# CRSC0003.net
KiCad netlist of a schematic drawn in Altium Designer
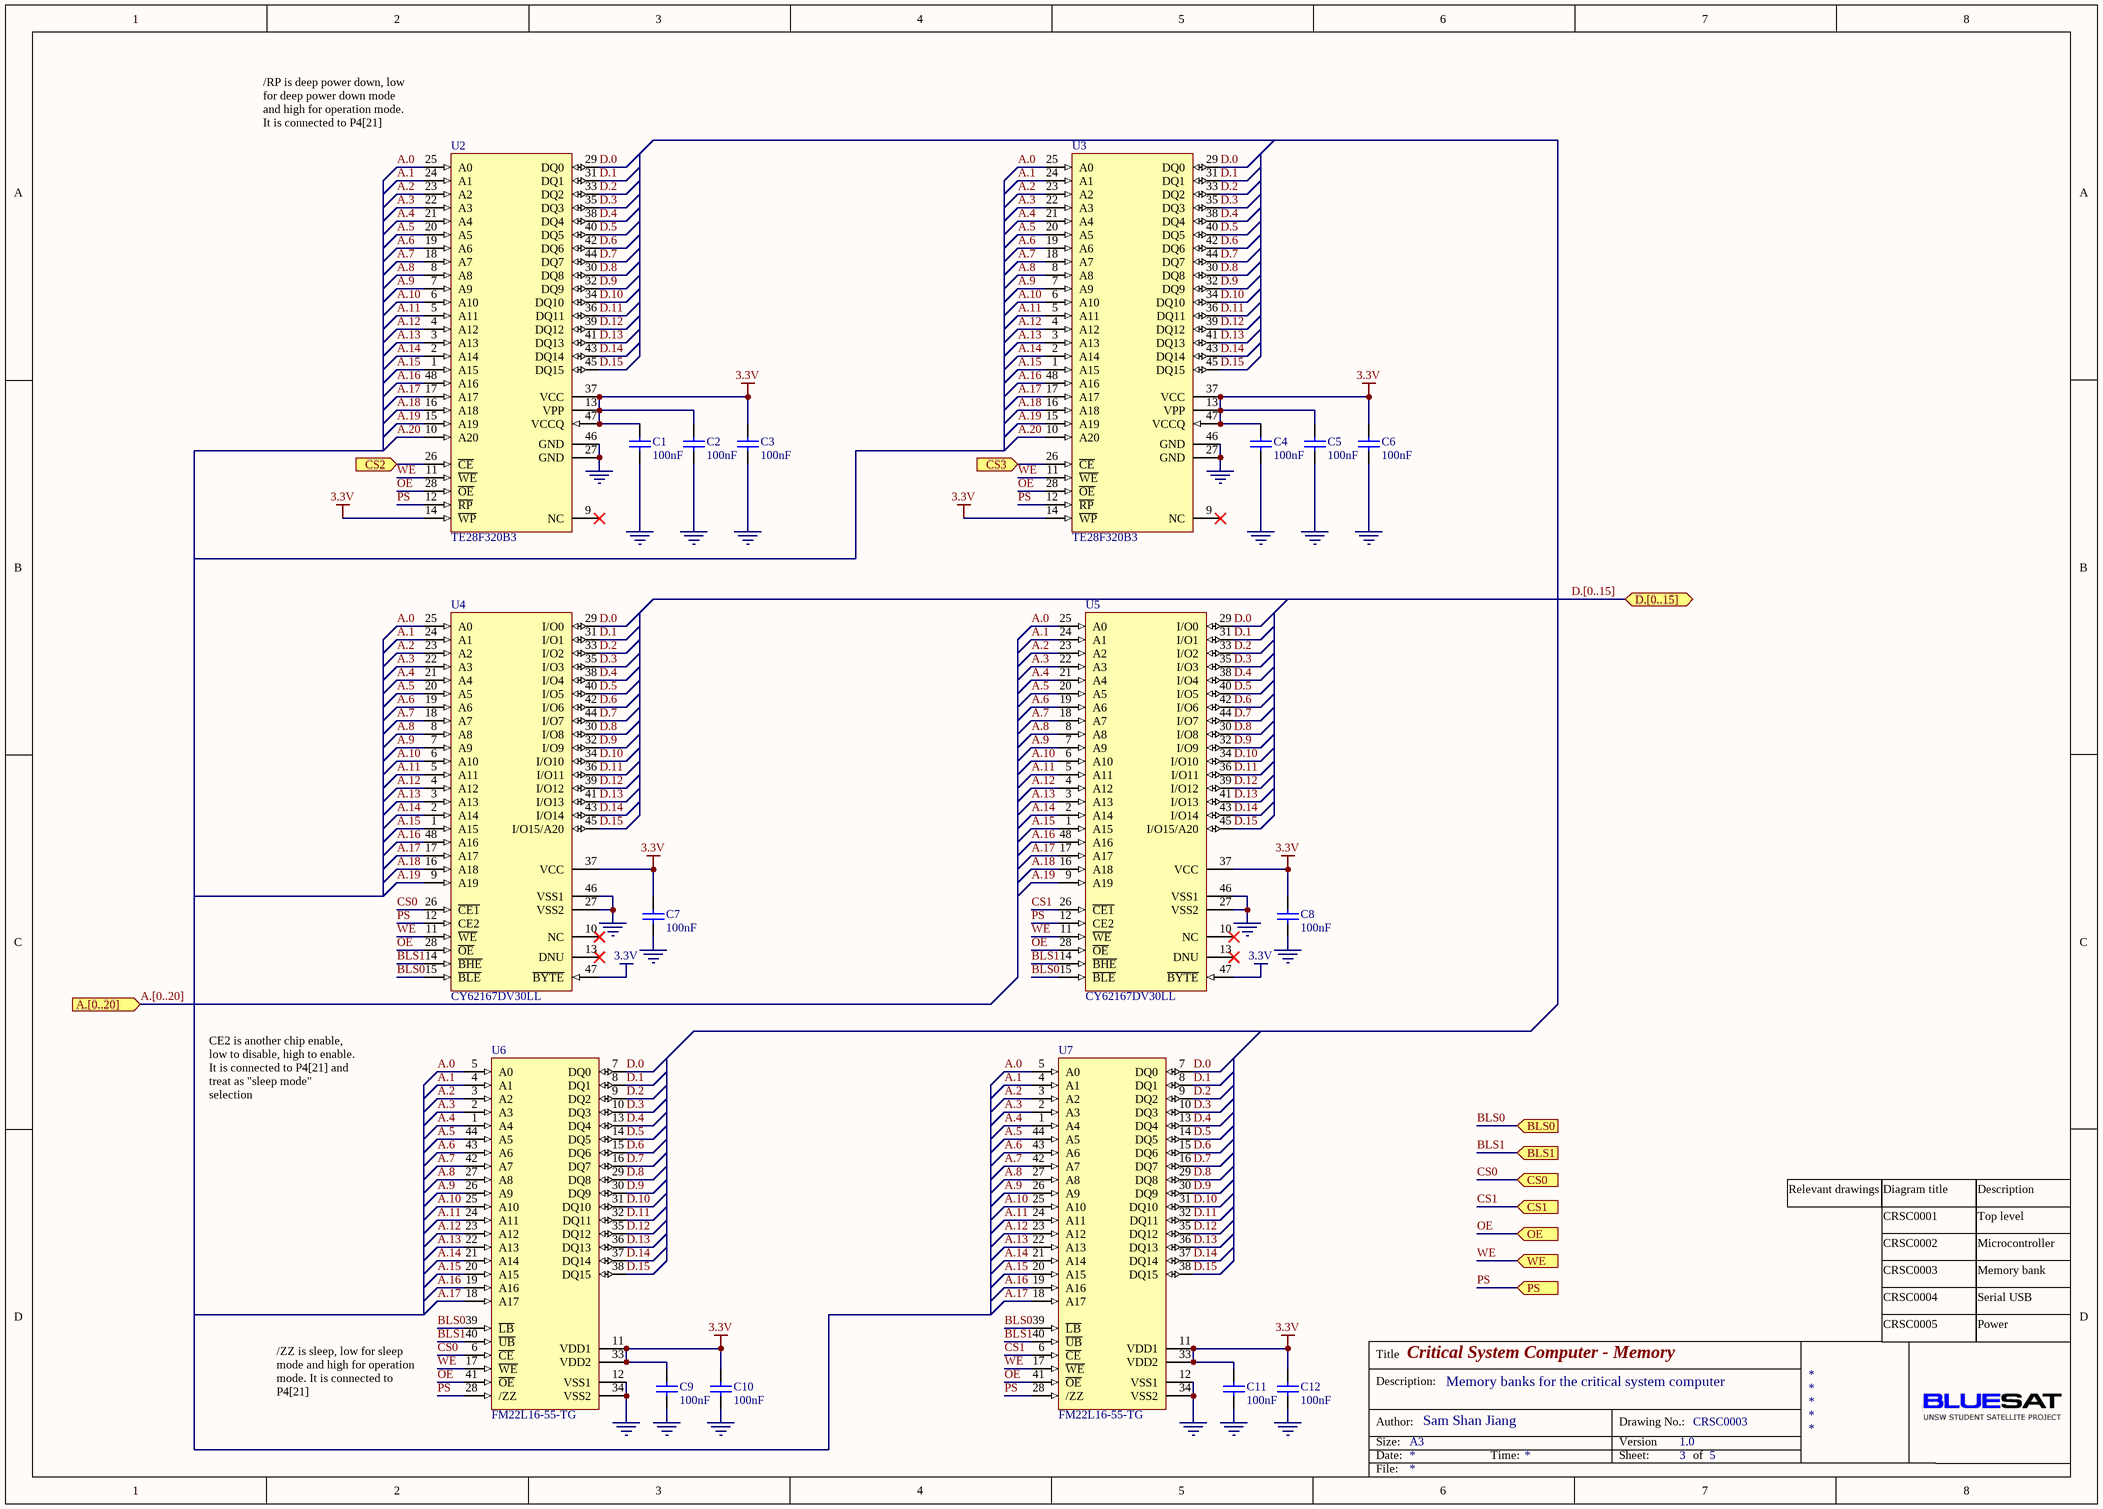
[diagram p0: CRSC0003.SchDoc]

(export (version "E")
  (design (tool "Eeschema 10.0.6"))
  (components
    (comp (ref "C1")
      (value "100nF")
      (footprint "0805")
      (description "Capacitor")
      (fields
        (field (name "MANUFACTURER") "Generic Components")
        (field (name "PUBLISHER") "Altium Hobart Technology Centre")
      )
      (libsource (lib "SELF-MADE_1004") (part "Cap"))
    )
    (comp (ref "C2")
      (value "100nF")
      (footprint "0805")
      (description "Capacitor")
      (fields
        (field (name "MANUFACTURER") "Generic Components")
        (field (name "PUBLISHER") "Altium Hobart Technology Centre")
      )
      (libsource (lib "SELF-MADE_1004") (part "Cap"))
    )
    (comp (ref "C3")
      (value "100nF")
      (footprint "0805")
      (description "Capacitor")
      (fields
        (field (name "MANUFACTURER") "Generic Components")
        (field (name "PUBLISHER") "Altium Hobart Technology Centre")
      )
      (libsource (lib "SELF-MADE_1004") (part "Cap"))
    )
    (comp (ref "C4")
      (value "100nF")
      (footprint "0805")
      (description "Capacitor")
      (fields
        (field (name "MANUFACTURER") "Generic Components")
        (field (name "PUBLISHER") "Altium Hobart Technology Centre")
      )
      (libsource (lib "SELF-MADE_1004") (part "Cap"))
    )
    (comp (ref "C5")
      (value "100nF")
      (footprint "0805")
      (description "Capacitor")
      (fields
        (field (name "MANUFACTURER") "Generic Components")
        (field (name "PUBLISHER") "Altium Hobart Technology Centre")
      )
      (libsource (lib "SELF-MADE_1004") (part "Cap"))
    )
    (comp (ref "C6")
      (value "100nF")
      (footprint "0805")
      (description "Capacitor")
      (fields
        (field (name "MANUFACTURER") "Generic Components")
        (field (name "PUBLISHER") "Altium Hobart Technology Centre")
      )
      (libsource (lib "SELF-MADE_1004") (part "Cap"))
    )
    (comp (ref "C7")
      (value "100nF")
      (footprint "0805")
      (description "Capacitor")
      (fields
        (field (name "MANUFACTURER") "Generic Components")
        (field (name "PUBLISHER") "Altium Hobart Technology Centre")
      )
      (libsource (lib "SELF-MADE_1004") (part "Cap"))
    )
    (comp (ref "C8")
      (value "100nF")
      (footprint "0805")
      (description "Capacitor")
      (fields
        (field (name "MANUFACTURER") "Generic Components")
        (field (name "PUBLISHER") "Altium Hobart Technology Centre")
      )
      (libsource (lib "SELF-MADE_1004") (part "Cap"))
    )
    (comp (ref "C9")
      (value "100nF")
      (footprint "0805")
      (description "Capacitor")
      (fields
        (field (name "MANUFACTURER") "Generic Components")
        (field (name "PUBLISHER") "Altium Hobart Technology Centre")
      )
      (libsource (lib "SELF-MADE_1004") (part "Cap"))
    )
    (comp (ref "C10")
      (value "100nF")
      (footprint "0805")
      (description "Capacitor")
      (fields
        (field (name "MANUFACTURER") "Generic Components")
        (field (name "PUBLISHER") "Altium Hobart Technology Centre")
      )
      (libsource (lib "SELF-MADE_1004") (part "Cap"))
    )
    (comp (ref "C11")
      (value "100nF")
      (footprint "0805")
      (description "Capacitor")
      (fields
        (field (name "MANUFACTURER") "Generic Components")
        (field (name "PUBLISHER") "Altium Hobart Technology Centre")
      )
      (libsource (lib "SELF-MADE_1004") (part "Cap"))
    )
    (comp (ref "C12")
      (value "100nF")
      (footprint "0805")
      (description "Capacitor")
      (fields
        (field (name "MANUFACTURER") "Generic Components")
        (field (name "PUBLISHER") "Altium Hobart Technology Centre")
      )
      (libsource (lib "SELF-MADE_1004") (part "Cap"))
    )
    (comp (ref "U2")
      (value "TE28F320B3")
      (footprint "TSOP48_L")
      (description "32-Mbit (2M x 16) Advanced Boot Block Flash Memory")
      (fields (field (name "PUBLISHER") "Altium Limited"))
      (libsource (lib "SELF-MADE_1505") (part "TE28F320B3"))
    )
    (comp (ref "U3")
      (value "TE28F320B3")
      (footprint "TSOP48_L")
      (description "32-Mbit (2M x 16) Advanced Boot Block Flash Memory")
      (fields (field (name "PUBLISHER") "Altium Limited"))
      (libsource (lib "SELF-MADE_1505") (part "TE28F320B3"))
    )
    (comp (ref "U4")
      (value "CY62167DV30LL")
      (footprint "TSOP48_L")
      (description "16-Mbit (1M x 16) Static RAM")
      (fields (field (name "PUBLISHER") "Altium Limited"))
      (libsource (lib "SELF-MADE_1505") (part "CY62167DV30LL"))
    )
    (comp (ref "U5")
      (value "CY62167DV30LL")
      (footprint "TSOP48_L")
      (description "16-Mbit (1M x 16) Static RAM")
      (fields (field (name "PUBLISHER") "Altium Limited"))
      (libsource (lib "SELF-MADE_1505") (part "CY62167DV30LL"))
    )
    (comp (ref "U6")
      (value "FM22L16-55-TG")
      (footprint "TSOP2-44_M")
      (description "FRAM, 2MB, 3V, 60NS, 44TSOP2")
      (libsource (lib "SELF-MADE_1004") (part "FM22L16-55-TG"))
    )
    (comp (ref "U7")
      (value "FM22L16-55-TG")
      (footprint "TSOP2-44_M")
      (description "FRAM, 2MB, 3V, 60NS, 44TSOP2")
      (libsource (lib "SELF-MADE_1004") (part "FM22L16-55-TG"))
    )
  )
  (nets
    (net (code "1") (name "/A.0") (class "Default")
      (node (ref "U2") (pin "25") (pinfunction "A0_25") (pintype "input"))
      (node (ref "U3") (pin "25") (pinfunction "A0_25") (pintype "input"))
      (node (ref "U4") (pin "25") (pinfunction "A0_25") (pintype "input"))
      (node (ref "U5") (pin "25") (pinfunction "A0_25") (pintype "input"))
      (node (ref "U6") (pin "5") (pinfunction "A0_5") (pintype "input"))
      (node (ref "U7") (pin "5") (pinfunction "A0_5") (pintype "input"))
    )
    (net (code "2") (name "/A.1") (class "Default")
      (node (ref "U2") (pin "24") (pinfunction "A1_24") (pintype "input"))
      (node (ref "U3") (pin "24") (pinfunction "A1_24") (pintype "input"))
      (node (ref "U4") (pin "24") (pinfunction "A1_24") (pintype "input"))
      (node (ref "U5") (pin "24") (pinfunction "A1_24") (pintype "input"))
      (node (ref "U6") (pin "4") (pinfunction "A1_4") (pintype "input"))
      (node (ref "U7") (pin "4") (pinfunction "A1_4") (pintype "input"))
    )
    (net (code "3") (name "/A.2") (class "Default")
      (node (ref "U2") (pin "23") (pinfunction "A2_23") (pintype "input"))
      (node (ref "U3") (pin "23") (pinfunction "A2_23") (pintype "input"))
      (node (ref "U4") (pin "23") (pinfunction "A2_23") (pintype "input"))
      (node (ref "U5") (pin "23") (pinfunction "A2_23") (pintype "input"))
      (node (ref "U6") (pin "3") (pinfunction "A2_3") (pintype "input"))
      (node (ref "U7") (pin "3") (pinfunction "A2_3") (pintype "input"))
    )
    (net (code "4") (name "/A.3") (class "Default")
      (node (ref "U2") (pin "22") (pinfunction "A3_22") (pintype "input"))
      (node (ref "U3") (pin "22") (pinfunction "A3_22") (pintype "input"))
      (node (ref "U4") (pin "22") (pinfunction "A3_22") (pintype "input"))
      (node (ref "U5") (pin "22") (pinfunction "A3_22") (pintype "input"))
      (node (ref "U6") (pin "2") (pinfunction "A3_2") (pintype "input"))
      (node (ref "U7") (pin "2") (pinfunction "A3_2") (pintype "input"))
    )
    (net (code "5") (name "/A.4") (class "Default")
      (node (ref "U2") (pin "21") (pinfunction "A4_21") (pintype "input"))
      (node (ref "U3") (pin "21") (pinfunction "A4_21") (pintype "input"))
      (node (ref "U4") (pin "21") (pinfunction "A4_21") (pintype "input"))
      (node (ref "U5") (pin "21") (pinfunction "A4_21") (pintype "input"))
      (node (ref "U6") (pin "1") (pinfunction "A4_1") (pintype "input"))
      (node (ref "U7") (pin "1") (pinfunction "A4_1") (pintype "input"))
    )
    (net (code "6") (name "/A.5") (class "Default")
      (node (ref "U2") (pin "20") (pinfunction "A5_20") (pintype "input"))
      (node (ref "U3") (pin "20") (pinfunction "A5_20") (pintype "input"))
      (node (ref "U4") (pin "20") (pinfunction "A5_20") (pintype "input"))
      (node (ref "U5") (pin "20") (pinfunction "A5_20") (pintype "input"))
      (node (ref "U6") (pin "44") (pinfunction "A5_44") (pintype "input"))
      (node (ref "U7") (pin "44") (pinfunction "A5_44") (pintype "input"))
    )
    (net (code "7") (name "/A.6") (class "Default")
      (node (ref "U2") (pin "19") (pinfunction "A6_19") (pintype "input"))
      (node (ref "U3") (pin "19") (pinfunction "A6_19") (pintype "input"))
      (node (ref "U4") (pin "19") (pinfunction "A6_19") (pintype "input"))
      (node (ref "U5") (pin "19") (pinfunction "A6_19") (pintype "input"))
      (node (ref "U6") (pin "43") (pinfunction "A6_43") (pintype "input"))
      (node (ref "U7") (pin "43") (pinfunction "A6_43") (pintype "input"))
    )
    (net (code "8") (name "/A.7") (class "Default")
      (node (ref "U2") (pin "18") (pinfunction "A7_18") (pintype "input"))
      (node (ref "U3") (pin "18") (pinfunction "A7_18") (pintype "input"))
      (node (ref "U4") (pin "18") (pinfunction "A7_18") (pintype "input"))
      (node (ref "U5") (pin "18") (pinfunction "A7_18") (pintype "input"))
      (node (ref "U6") (pin "42") (pinfunction "A7_42") (pintype "input"))
      (node (ref "U7") (pin "42") (pinfunction "A7_42") (pintype "input"))
    )
    (net (code "9") (name "/A.8") (class "Default")
      (node (ref "U2") (pin "8") (pinfunction "A8_8") (pintype "input"))
      (node (ref "U3") (pin "8") (pinfunction "A8_8") (pintype "input"))
      (node (ref "U4") (pin "8") (pinfunction "A8_8") (pintype "input"))
      (node (ref "U5") (pin "8") (pinfunction "A8_8") (pintype "input"))
      (node (ref "U6") (pin "27") (pinfunction "A8_27") (pintype "input"))
      (node (ref "U7") (pin "27") (pinfunction "A8_27") (pintype "input"))
    )
    (net (code "10") (name "/A.9") (class "Default")
      (node (ref "U2") (pin "7") (pinfunction "A9_7") (pintype "input"))
      (node (ref "U3") (pin "7") (pinfunction "A9_7") (pintype "input"))
      (node (ref "U4") (pin "7") (pinfunction "A9_7") (pintype "input"))
      (node (ref "U5") (pin "7") (pinfunction "A9_7") (pintype "input"))
      (node (ref "U6") (pin "26") (pinfunction "A9_26") (pintype "input"))
      (node (ref "U7") (pin "26") (pinfunction "A9_26") (pintype "input"))
    )
    (net (code "11") (name "/A.10") (class "Default")
      (node (ref "U2") (pin "6") (pinfunction "A10_6") (pintype "input"))
      (node (ref "U3") (pin "6") (pinfunction "A10_6") (pintype "input"))
      (node (ref "U4") (pin "6") (pinfunction "A10_6") (pintype "input"))
      (node (ref "U5") (pin "6") (pinfunction "A10_6") (pintype "input"))
      (node (ref "U6") (pin "25") (pinfunction "A10_25") (pintype "input"))
      (node (ref "U7") (pin "25") (pinfunction "A10_25") (pintype "input"))
    )
    (net (code "12") (name "/A.11") (class "Default")
      (node (ref "U2") (pin "5") (pinfunction "A11_5") (pintype "input"))
      (node (ref "U3") (pin "5") (pinfunction "A11_5") (pintype "input"))
      (node (ref "U4") (pin "5") (pinfunction "A11_5") (pintype "input"))
      (node (ref "U5") (pin "5") (pinfunction "A11_5") (pintype "input"))
      (node (ref "U6") (pin "24") (pinfunction "A11_24") (pintype "input"))
      (node (ref "U7") (pin "24") (pinfunction "A11_24") (pintype "input"))
    )
    (net (code "13") (name "/A.12") (class "Default")
      (node (ref "U2") (pin "4") (pinfunction "A12_4") (pintype "input"))
      (node (ref "U3") (pin "4") (pinfunction "A12_4") (pintype "input"))
      (node (ref "U4") (pin "4") (pinfunction "A12_4") (pintype "input"))
      (node (ref "U5") (pin "4") (pinfunction "A12_4") (pintype "input"))
      (node (ref "U6") (pin "23") (pinfunction "A12_23") (pintype "input"))
      (node (ref "U7") (pin "23") (pinfunction "A12_23") (pintype "input"))
    )
    (net (code "14") (name "/A.13") (class "Default")
      (node (ref "U2") (pin "3") (pinfunction "A13_3") (pintype "input"))
      (node (ref "U3") (pin "3") (pinfunction "A13_3") (pintype "input"))
      (node (ref "U4") (pin "3") (pinfunction "A13_3") (pintype "input"))
      (node (ref "U5") (pin "3") (pinfunction "A13_3") (pintype "input"))
      (node (ref "U6") (pin "22") (pinfunction "A13_22") (pintype "input"))
      (node (ref "U7") (pin "22") (pinfunction "A13_22") (pintype "input"))
    )
    (net (code "15") (name "/A.14") (class "Default")
      (node (ref "U2") (pin "2") (pinfunction "A14_2") (pintype "input"))
      (node (ref "U3") (pin "2") (pinfunction "A14_2") (pintype "input"))
      (node (ref "U4") (pin "2") (pinfunction "A14_2") (pintype "input"))
      (node (ref "U5") (pin "2") (pinfunction "A14_2") (pintype "input"))
      (node (ref "U6") (pin "21") (pinfunction "A14_21") (pintype "input"))
      (node (ref "U7") (pin "21") (pinfunction "A14_21") (pintype "input"))
    )
    (net (code "16") (name "/A.15") (class "Default")
      (node (ref "U2") (pin "1") (pinfunction "A15_1") (pintype "input"))
      (node (ref "U3") (pin "1") (pinfunction "A15_1") (pintype "input"))
      (node (ref "U4") (pin "1") (pinfunction "A15_1") (pintype "input"))
      (node (ref "U5") (pin "1") (pinfunction "A15_1") (pintype "input"))
      (node (ref "U6") (pin "20") (pinfunction "A15_20") (pintype "input"))
      (node (ref "U7") (pin "20") (pinfunction "A15_20") (pintype "input"))
    )
    (net (code "17") (name "/A.16") (class "Default")
      (node (ref "U2") (pin "48") (pinfunction "A16_48") (pintype "input"))
      (node (ref "U3") (pin "48") (pinfunction "A16_48") (pintype "input"))
      (node (ref "U4") (pin "48") (pinfunction "A16_48") (pintype "input"))
      (node (ref "U5") (pin "48") (pinfunction "A16_48") (pintype "input"))
      (node (ref "U6") (pin "19") (pinfunction "A16_19") (pintype "input"))
      (node (ref "U7") (pin "19") (pinfunction "A16_19") (pintype "input"))
    )
    (net (code "18") (name "/A.17") (class "Default")
      (node (ref "U2") (pin "17") (pinfunction "A17_17") (pintype "input"))
      (node (ref "U3") (pin "17") (pinfunction "A17_17") (pintype "input"))
      (node (ref "U4") (pin "17") (pinfunction "A17_17") (pintype "input"))
      (node (ref "U5") (pin "17") (pinfunction "A17_17") (pintype "input"))
      (node (ref "U6") (pin "18") (pinfunction "A17_18") (pintype "input"))
      (node (ref "U7") (pin "18") (pinfunction "A17_18") (pintype "input"))
    )
    (net (code "19") (name "/A.18") (class "Default")
      (node (ref "U2") (pin "16") (pinfunction "A18_16") (pintype "input"))
      (node (ref "U3") (pin "16") (pinfunction "A18_16") (pintype "input"))
      (node (ref "U4") (pin "16") (pinfunction "A18_16") (pintype "input"))
      (node (ref "U5") (pin "16") (pinfunction "A18_16") (pintype "input"))
    )
    (net (code "20") (name "/A.19") (class "Default")
      (node (ref "U2") (pin "15") (pinfunction "A19_15") (pintype "input"))
      (node (ref "U3") (pin "15") (pinfunction "A19_15") (pintype "input"))
      (node (ref "U4") (pin "9") (pinfunction "A19_9") (pintype "input"))
      (node (ref "U5") (pin "9") (pinfunction "A19_9") (pintype "input"))
    )
    (net (code "21") (name "/A.20") (class "Default")
      (node (ref "U2") (pin "10") (pinfunction "A20_10") (pintype "input"))
      (node (ref "U3") (pin "10") (pinfunction "A20_10") (pintype "input"))
    )
    (net (code "23") (name "/BLS0") (class "Default")
      (node (ref "U4") (pin "15") (pinfunction "~{BLE}_15") (pintype "input"))
      (node (ref "U5") (pin "15") (pinfunction "~{BLE}_15") (pintype "input"))
      (node (ref "U6") (pin "39") (pinfunction "~{LB}_39") (pintype "input"))
      (node (ref "U7") (pin "39") (pinfunction "~{LB}_39") (pintype "input"))
    )
    (net (code "24") (name "/BLS1") (class "Default")
      (node (ref "U4") (pin "14") (pinfunction "~{BHE}_14") (pintype "input"))
      (node (ref "U5") (pin "14") (pinfunction "~{BHE}_14") (pintype "input"))
      (node (ref "U6") (pin "40") (pinfunction "~{UB}_40") (pintype "input"))
      (node (ref "U7") (pin "40") (pinfunction "~{UB}_40") (pintype "input"))
    )
    (net (code "25") (name "/CS0") (class "Default")
      (node (ref "U4") (pin "26") (pinfunction "~{CE1}_26") (pintype "input"))
      (node (ref "U6") (pin "6") (pinfunction "~{CE}_6") (pintype "input"))
    )
    (net (code "26") (name "/CS1") (class "Default")
      (node (ref "U5") (pin "26") (pinfunction "~{CE1}_26") (pintype "input"))
      (node (ref "U7") (pin "6") (pinfunction "~{CE}_6") (pintype "input"))
    )
    (net (code "27") (name "/CS2") (class "Default")
      (node (ref "U2") (pin "26") (pinfunction "~{CE}_26") (pintype "input"))
    )
    (net (code "28") (name "/CS3") (class "Default")
      (node (ref "U3") (pin "26") (pinfunction "~{CE}_26") (pintype "input"))
    )
    (net (code "29") (name "/D.0") (class "Default")
      (node (ref "U2") (pin "29") (pinfunction "DQ0_29") (pintype "bidirectional"))
      (node (ref "U3") (pin "29") (pinfunction "DQ0_29") (pintype "bidirectional"))
      (node (ref "U4") (pin "29") (pinfunction "I/O0_29") (pintype "bidirectional"))
      (node (ref "U5") (pin "29") (pinfunction "I/O0_29") (pintype "bidirectional"))
      (node (ref "U6") (pin "7") (pinfunction "DQ0_7") (pintype "bidirectional"))
      (node (ref "U7") (pin "7") (pinfunction "DQ0_7") (pintype "bidirectional"))
    )
    (net (code "30") (name "/D.1") (class "Default")
      (node (ref "U2") (pin "31") (pinfunction "DQ1_31") (pintype "bidirectional"))
      (node (ref "U3") (pin "31") (pinfunction "DQ1_31") (pintype "bidirectional"))
      (node (ref "U4") (pin "31") (pinfunction "I/O1_31") (pintype "bidirectional"))
      (node (ref "U5") (pin "31") (pinfunction "I/O1_31") (pintype "bidirectional"))
      (node (ref "U6") (pin "8") (pinfunction "DQ1_8") (pintype "bidirectional"))
      (node (ref "U7") (pin "8") (pinfunction "DQ1_8") (pintype "bidirectional"))
    )
    (net (code "31") (name "/D.2") (class "Default")
      (node (ref "U2") (pin "33") (pinfunction "DQ2_33") (pintype "bidirectional"))
      (node (ref "U3") (pin "33") (pinfunction "DQ2_33") (pintype "bidirectional"))
      (node (ref "U4") (pin "33") (pinfunction "I/O2_33") (pintype "bidirectional"))
      (node (ref "U5") (pin "33") (pinfunction "I/O2_33") (pintype "bidirectional"))
      (node (ref "U6") (pin "9") (pinfunction "DQ2_9") (pintype "bidirectional"))
      (node (ref "U7") (pin "9") (pinfunction "DQ2_9") (pintype "bidirectional"))
    )
    (net (code "32") (name "/D.3") (class "Default")
      (node (ref "U2") (pin "35") (pinfunction "DQ3_35") (pintype "bidirectional"))
      (node (ref "U3") (pin "35") (pinfunction "DQ3_35") (pintype "bidirectional"))
      (node (ref "U4") (pin "35") (pinfunction "I/O3_35") (pintype "bidirectional"))
      (node (ref "U5") (pin "35") (pinfunction "I/O3_35") (pintype "bidirectional"))
      (node (ref "U6") (pin "10") (pinfunction "DQ3_10") (pintype "bidirectional"))
      (node (ref "U7") (pin "10") (pinfunction "DQ3_10") (pintype "bidirectional"))
    )
    (net (code "33") (name "/D.4") (class "Default")
      (node (ref "U2") (pin "38") (pinfunction "DQ4_38") (pintype "bidirectional"))
      (node (ref "U3") (pin "38") (pinfunction "DQ4_38") (pintype "bidirectional"))
      (node (ref "U4") (pin "38") (pinfunction "I/O4_38") (pintype "bidirectional"))
      (node (ref "U5") (pin "38") (pinfunction "I/O4_38") (pintype "bidirectional"))
      (node (ref "U6") (pin "13") (pinfunction "DQ4_13") (pintype "bidirectional"))
      (node (ref "U7") (pin "13") (pinfunction "DQ4_13") (pintype "bidirectional"))
    )
    (net (code "34") (name "/D.5") (class "Default")
      (node (ref "U2") (pin "40") (pinfunction "DQ5_40") (pintype "bidirectional"))
      (node (ref "U3") (pin "40") (pinfunction "DQ5_40") (pintype "bidirectional"))
      (node (ref "U4") (pin "40") (pinfunction "I/O5_40") (pintype "bidirectional"))
      (node (ref "U5") (pin "40") (pinfunction "I/O5_40") (pintype "bidirectional"))
      (node (ref "U6") (pin "14") (pinfunction "DQ5_14") (pintype "bidirectional"))
      (node (ref "U7") (pin "14") (pinfunction "DQ5_14") (pintype "bidirectional"))
    )
    (net (code "35") (name "/D.6") (class "Default")
      (node (ref "U2") (pin "42") (pinfunction "DQ6_42") (pintype "bidirectional"))
      (node (ref "U3") (pin "42") (pinfunction "DQ6_42") (pintype "bidirectional"))
      (node (ref "U4") (pin "42") (pinfunction "I/O6_42") (pintype "bidirectional"))
      (node (ref "U5") (pin "42") (pinfunction "I/O6_42") (pintype "bidirectional"))
      (node (ref "U6") (pin "15") (pinfunction "DQ6_15") (pintype "bidirectional"))
      (node (ref "U7") (pin "15") (pinfunction "DQ6_15") (pintype "bidirectional"))
    )
    (net (code "36") (name "/D.7") (class "Default")
      (node (ref "U2") (pin "44") (pinfunction "DQ7_44") (pintype "bidirectional"))
      (node (ref "U3") (pin "44") (pinfunction "DQ7_44") (pintype "bidirectional"))
      (node (ref "U4") (pin "44") (pinfunction "I/O7_44") (pintype "bidirectional"))
      (node (ref "U5") (pin "44") (pinfunction "I/O7_44") (pintype "bidirectional"))
      (node (ref "U6") (pin "16") (pinfunction "DQ7_16") (pintype "bidirectional"))
      (node (ref "U7") (pin "16") (pinfunction "DQ7_16") (pintype "bidirectional"))
    )
    (net (code "37") (name "/D.8") (class "Default")
      (node (ref "U2") (pin "30") (pinfunction "DQ8_30") (pintype "bidirectional"))
      (node (ref "U3") (pin "30") (pinfunction "DQ8_30") (pintype "bidirectional"))
      (node (ref "U4") (pin "30") (pinfunction "I/O8_30") (pintype "bidirectional"))
      (node (ref "U5") (pin "30") (pinfunction "I/O8_30") (pintype "bidirectional"))
      (node (ref "U6") (pin "29") (pinfunction "DQ8_29") (pintype "bidirectional"))
      (node (ref "U7") (pin "29") (pinfunction "DQ8_29") (pintype "bidirectional"))
    )
    (net (code "38") (name "/D.9") (class "Default")
      (node (ref "U2") (pin "32") (pinfunction "DQ9_32") (pintype "bidirectional"))
      (node (ref "U3") (pin "32") (pinfunction "DQ9_32") (pintype "bidirectional"))
      (node (ref "U4") (pin "32") (pinfunction "I/O9_32") (pintype "bidirectional"))
      (node (ref "U5") (pin "32") (pinfunction "I/O9_32") (pintype "bidirectional"))
      (node (ref "U6") (pin "30") (pinfunction "DQ9_30") (pintype "bidirectional"))
      (node (ref "U7") (pin "30") (pinfunction "DQ9_30") (pintype "bidirectional"))
    )
    (net (code "39") (name "/D.10") (class "Default")
      (node (ref "U2") (pin "34") (pinfunction "DQ10_34") (pintype "bidirectional"))
      (node (ref "U3") (pin "34") (pinfunction "DQ10_34") (pintype "bidirectional"))
      (node (ref "U4") (pin "34") (pinfunction "I/O10_34") (pintype "bidirectional"))
      (node (ref "U5") (pin "34") (pinfunction "I/O10_34") (pintype "bidirectional"))
      (node (ref "U6") (pin "31") (pinfunction "DQ10_31") (pintype "bidirectional"))
      (node (ref "U7") (pin "31") (pinfunction "DQ10_31") (pintype "bidirectional"))
    )
    (net (code "40") (name "/D.11") (class "Default")
      (node (ref "U2") (pin "36") (pinfunction "DQ11_36") (pintype "bidirectional"))
      (node (ref "U3") (pin "36") (pinfunction "DQ11_36") (pintype "bidirectional"))
      (node (ref "U4") (pin "36") (pinfunction "I/O11_36") (pintype "bidirectional"))
      (node (ref "U5") (pin "36") (pinfunction "I/O11_36") (pintype "bidirectional"))
      (node (ref "U6") (pin "32") (pinfunction "DQ11_32") (pintype "bidirectional"))
      (node (ref "U7") (pin "32") (pinfunction "DQ11_32") (pintype "bidirectional"))
    )
    (net (code "41") (name "/D.12") (class "Default")
      (node (ref "U2") (pin "39") (pinfunction "DQ12_39") (pintype "bidirectional"))
      (node (ref "U3") (pin "39") (pinfunction "DQ12_39") (pintype "bidirectional"))
      (node (ref "U4") (pin "39") (pinfunction "I/O12_39") (pintype "bidirectional"))
      (node (ref "U5") (pin "39") (pinfunction "I/O12_39") (pintype "bidirectional"))
      (node (ref "U6") (pin "35") (pinfunction "DQ12_35") (pintype "bidirectional"))
      (node (ref "U7") (pin "35") (pinfunction "DQ12_35") (pintype "bidirectional"))
    )
    (net (code "42") (name "/D.13") (class "Default")
      (node (ref "U2") (pin "41") (pinfunction "DQ13_41") (pintype "bidirectional"))
      (node (ref "U3") (pin "41") (pinfunction "DQ13_41") (pintype "bidirectional"))
      (node (ref "U4") (pin "41") (pinfunction "I/O13_41") (pintype "bidirectional"))
      (node (ref "U5") (pin "41") (pinfunction "I/O13_41") (pintype "bidirectional"))
      (node (ref "U6") (pin "36") (pinfunction "DQ13_36") (pintype "bidirectional"))
      (node (ref "U7") (pin "36") (pinfunction "DQ13_36") (pintype "bidirectional"))
    )
    (net (code "43") (name "/D.14") (class "Default")
      (node (ref "U2") (pin "43") (pinfunction "DQ14_43") (pintype "bidirectional"))
      (node (ref "U3") (pin "43") (pinfunction "DQ14_43") (pintype "bidirectional"))
      (node (ref "U4") (pin "43") (pinfunction "I/O14_43") (pintype "bidirectional"))
      (node (ref "U5") (pin "43") (pinfunction "I/O14_43") (pintype "bidirectional"))
      (node (ref "U6") (pin "37") (pinfunction "DQ14_37") (pintype "bidirectional"))
      (node (ref "U7") (pin "37") (pinfunction "DQ14_37") (pintype "bidirectional"))
    )
    (net (code "44") (name "/D.15") (class "Default")
      (node (ref "U2") (pin "45") (pinfunction "DQ15_45") (pintype "bidirectional"))
      (node (ref "U3") (pin "45") (pinfunction "DQ15_45") (pintype "bidirectional"))
      (node (ref "U4") (pin "45") (pinfunction "I/O15/A20_45") (pintype "bidirectional"))
      (node (ref "U5") (pin "45") (pinfunction "I/O15/A20_45") (pintype "bidirectional"))
      (node (ref "U6") (pin "38") (pinfunction "DQ15_38") (pintype "bidirectional"))
      (node (ref "U7") (pin "38") (pinfunction "DQ15_38") (pintype "bidirectional"))
    )
    (net (code "46") (name "/OE") (class "Default")
      (node (ref "U2") (pin "28") (pinfunction "~{OE}_28") (pintype "input"))
      (node (ref "U3") (pin "28") (pinfunction "~{OE}_28") (pintype "input"))
      (node (ref "U4") (pin "28") (pinfunction "~{OE}_28") (pintype "input"))
      (node (ref "U5") (pin "28") (pinfunction "~{OE}_28") (pintype "input"))
      (node (ref "U6") (pin "41") (pinfunction "~{OE}_41") (pintype "input"))
      (node (ref "U7") (pin "41") (pinfunction "~{OE}_41") (pintype "input"))
    )
    (net (code "47") (name "/PS") (class "Default")
      (node (ref "U2") (pin "12") (pinfunction "~{RP}_12") (pintype "input"))
      (node (ref "U3") (pin "12") (pinfunction "~{RP}_12") (pintype "input"))
      (node (ref "U4") (pin "12") (pinfunction "CE2_12") (pintype "input"))
      (node (ref "U5") (pin "12") (pinfunction "CE2_12") (pintype "input"))
      (node (ref "U6") (pin "28") (pinfunction "/ZZ_28") (pintype "input"))
      (node (ref "U7") (pin "28") (pinfunction "/ZZ_28") (pintype "input"))
    )
    (net (code "48") (name "/WE") (class "Default")
      (node (ref "U2") (pin "11") (pinfunction "~{WE}_11") (pintype "input"))
      (node (ref "U3") (pin "11") (pinfunction "~{WE}_11") (pintype "input"))
      (node (ref "U4") (pin "11") (pinfunction "~{WE}_11") (pintype "input"))
      (node (ref "U5") (pin "11") (pinfunction "~{WE}_11") (pintype "input"))
      (node (ref "U6") (pin "17") (pinfunction "~{WE}_17") (pintype "input"))
      (node (ref "U7") (pin "17") (pinfunction "~{WE}_17") (pintype "input"))
    )
    (net (code "49") (name "3.3V") (class "Default")
      (node (ref "C1") (pin "2") (pinfunction "2_2") (pintype "passive"))
      (node (ref "C10") (pin "2") (pinfunction "2_2") (pintype "passive"))
      (node (ref "C11") (pin "2") (pinfunction "2_2") (pintype "passive"))
      (node (ref "C12") (pin "2") (pinfunction "2_2") (pintype "passive"))
      (node (ref "C2") (pin "2") (pinfunction "2_2") (pintype "passive"))
      (node (ref "C3") (pin "2") (pinfunction "2_2") (pintype "passive"))
      (node (ref "C4") (pin "2") (pinfunction "2_2") (pintype "passive"))
      (node (ref "C5") (pin "2") (pinfunction "2_2") (pintype "passive"))
      (node (ref "C6") (pin "2") (pinfunction "2_2") (pintype "passive"))
      (node (ref "C7") (pin "2") (pinfunction "2_2") (pintype "passive"))
      (node (ref "C8") (pin "2") (pinfunction "2_2") (pintype "passive"))
      (node (ref "C9") (pin "2") (pinfunction "2_2") (pintype "passive"))
      (node (ref "U2") (pin "13") (pinfunction "VPP_13") (pintype "power_in"))
      (node (ref "U2") (pin "14") (pinfunction "~{WP}_14") (pintype "input"))
      (node (ref "U2") (pin "37") (pinfunction "VCC_37") (pintype "power_in"))
      (node (ref "U2") (pin "47") (pinfunction "VCCQ_47") (pintype "input"))
      (node (ref "U3") (pin "13") (pinfunction "VPP_13") (pintype "power_in"))
      (node (ref "U3") (pin "14") (pinfunction "~{WP}_14") (pintype "input"))
      (node (ref "U3") (pin "37") (pinfunction "VCC_37") (pintype "power_in"))
      (node (ref "U3") (pin "47") (pinfunction "VCCQ_47") (pintype "input"))
      (node (ref "U4") (pin "37") (pinfunction "VCC_37") (pintype "power_in"))
      (node (ref "U4") (pin "47") (pinfunction "~{BYTE}_47") (pintype "input"))
      (node (ref "U5") (pin "37") (pinfunction "VCC_37") (pintype "power_in"))
      (node (ref "U5") (pin "47") (pinfunction "~{BYTE}_47") (pintype "input"))
      (node (ref "U6") (pin "11") (pinfunction "VDD1_11") (pintype "power_in"))
      (node (ref "U6") (pin "33") (pinfunction "VDD2_33") (pintype "power_in"))
      (node (ref "U7") (pin "11") (pinfunction "VDD1_11") (pintype "power_in"))
      (node (ref "U7") (pin "33") (pinfunction "VDD2_33") (pintype "power_in"))
    )
    (net (code "50") (name "GND") (class "Default")
      (node (ref "C1") (pin "1") (pinfunction "1_1") (pintype "passive"))
      (node (ref "C10") (pin "1") (pinfunction "1_1") (pintype "passive"))
      (node (ref "C11") (pin "1") (pinfunction "1_1") (pintype "passive"))
      (node (ref "C12") (pin "1") (pinfunction "1_1") (pintype "passive"))
      (node (ref "C2") (pin "1") (pinfunction "1_1") (pintype "passive"))
      (node (ref "C3") (pin "1") (pinfunction "1_1") (pintype "passive"))
      (node (ref "C4") (pin "1") (pinfunction "1_1") (pintype "passive"))
      (node (ref "C5") (pin "1") (pinfunction "1_1") (pintype "passive"))
      (node (ref "C6") (pin "1") (pinfunction "1_1") (pintype "passive"))
      (node (ref "C7") (pin "1") (pinfunction "1_1") (pintype "passive"))
      (node (ref "C8") (pin "1") (pinfunction "1_1") (pintype "passive"))
      (node (ref "C9") (pin "1") (pinfunction "1_1") (pintype "passive"))
      (node (ref "U2") (pin "27") (pinfunction "GND_27") (pintype "power_in"))
      (node (ref "U2") (pin "46") (pinfunction "GND_46") (pintype "power_in"))
      (node (ref "U3") (pin "27") (pinfunction "GND_27") (pintype "power_in"))
      (node (ref "U3") (pin "46") (pinfunction "GND_46") (pintype "power_in"))
      (node (ref "U4") (pin "27") (pinfunction "VSS2_27") (pintype "power_in"))
      (node (ref "U4") (pin "46") (pinfunction "VSS1_46") (pintype "power_in"))
      (node (ref "U5") (pin "27") (pinfunction "VSS2_27") (pintype "power_in"))
      (node (ref "U5") (pin "46") (pinfunction "VSS1_46") (pintype "power_in"))
      (node (ref "U6") (pin "12") (pinfunction "VSS1_12") (pintype "power_in"))
      (node (ref "U6") (pin "34") (pinfunction "VSS2_34") (pintype "power_in"))
      (node (ref "U7") (pin "12") (pinfunction "VSS1_12") (pintype "power_in"))
      (node (ref "U7") (pin "34") (pinfunction "VSS2_34") (pintype "power_in"))
    )
    (net (code "51") (name "unconnected-(U2-NC-Pad9)") (class "Default")
      (node (ref "U2") (pin "9") (pinfunction "NC_9") (pintype "passive+no_connect"))
    )
    (net (code "52") (name "unconnected-(U3-NC-Pad9)") (class "Default")
      (node (ref "U3") (pin "9") (pinfunction "NC_9") (pintype "passive+no_connect"))
    )
    (net (code "53") (name "unconnected-(U4-DNU-Pad13)") (class "Default")
      (node (ref "U4") (pin "13") (pinfunction "DNU_13") (pintype "passive+no_connect"))
    )
    (net (code "54") (name "unconnected-(U4-NC-Pad10)") (class "Default")
      (node (ref "U4") (pin "10") (pinfunction "NC_10") (pintype "passive+no_connect"))
    )
    (net (code "55") (name "unconnected-(U5-DNU-Pad13)") (class "Default")
      (node (ref "U5") (pin "13") (pinfunction "DNU_13") (pintype "passive+no_connect"))
    )
    (net (code "56") (name "unconnected-(U5-NC-Pad10)") (class "Default")
      (node (ref "U5") (pin "10") (pinfunction "NC_10") (pintype "passive+no_connect"))
    )
  )
)
